# tsal_v1.net
KiCad netlist of a schematic drawn in Altium Designer
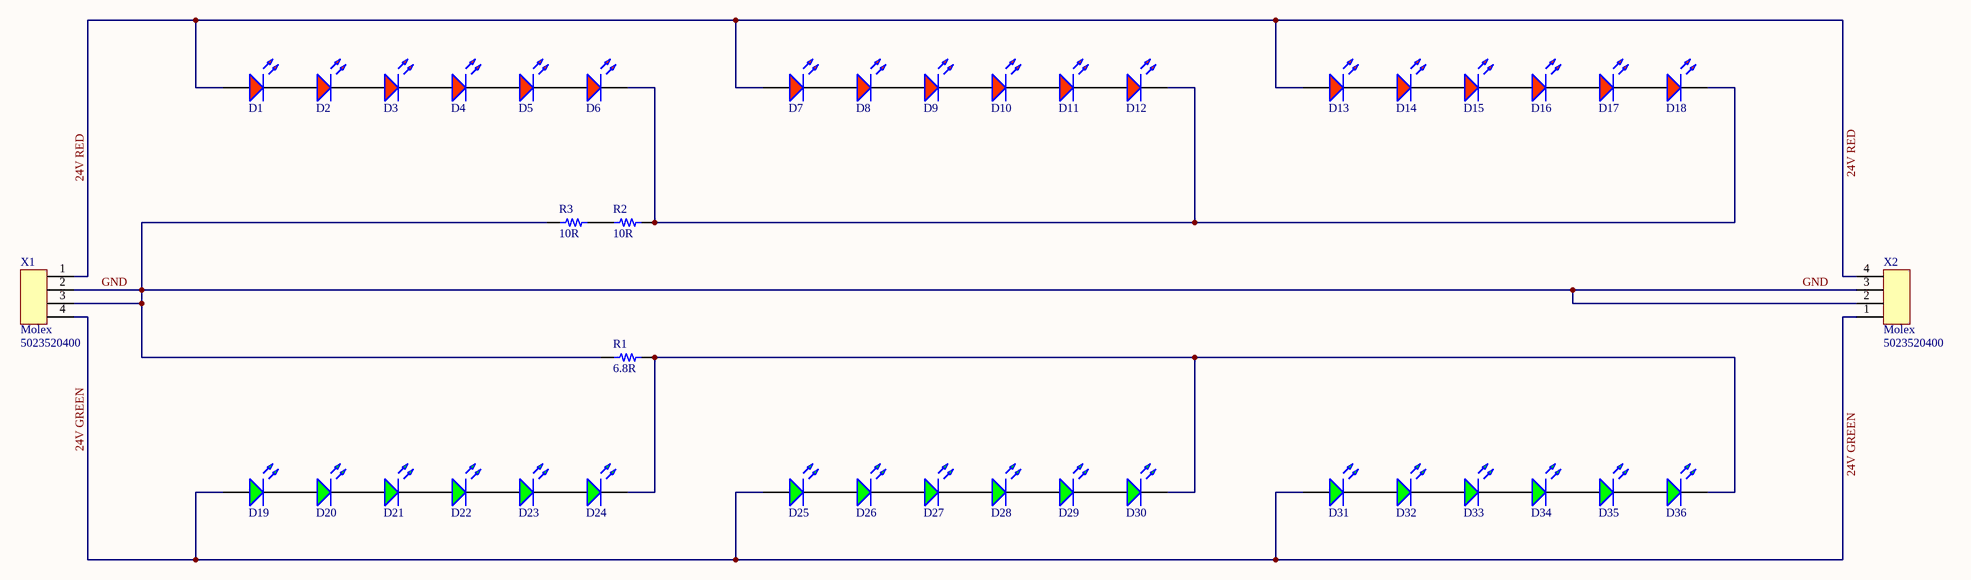
[diagram p0: tsal_v1.SchDoc]

(export (version "E")
  (design (tool "Eeschema 10.0.6"))
  (components
    (comp (ref "D1")
      (value "LED XLAMP RED 1616 SMD")
      (footprint "led red 0606")
      (description "LED Lighting Color Xlamp® XQ-A Red 625nm (620nm ~ 630nm) 0606 (1616 Metric)")
      (fields
        (field (name "MANUFACTURER") "Comchip Technology")
        (field (name "PART_NUMBER") "XQARED-02-0000-000000W01")
      )
      (libsource (lib "Diodes") (part "XQARED-02-0000-000000W01"))
    )
    (comp (ref "D2")
      (value "LED XLAMP RED 1616 SMD")
      (footprint "led red 0606")
      (description "LED Lighting Color Xlamp® XQ-A Red 625nm (620nm ~ 630nm) 0606 (1616 Metric)")
      (fields
        (field (name "MANUFACTURER") "Comchip Technology")
        (field (name "PART_NUMBER") "XQARED-02-0000-000000W01")
      )
      (libsource (lib "Diodes") (part "XQARED-02-0000-000000W01"))
    )
    (comp (ref "D3")
      (value "LED XLAMP RED 1616 SMD")
      (footprint "led red 0606")
      (description "LED Lighting Color Xlamp® XQ-A Red 625nm (620nm ~ 630nm) 0606 (1616 Metric)")
      (fields
        (field (name "MANUFACTURER") "Comchip Technology")
        (field (name "PART_NUMBER") "XQARED-02-0000-000000W01")
      )
      (libsource (lib "Diodes") (part "XQARED-02-0000-000000W01"))
    )
    (comp (ref "D4")
      (value "LED XLAMP RED 1616 SMD")
      (footprint "led red 0606")
      (description "LED Lighting Color Xlamp® XQ-A Red 625nm (620nm ~ 630nm) 0606 (1616 Metric)")
      (fields
        (field (name "MANUFACTURER") "Comchip Technology")
        (field (name "PART_NUMBER") "XQARED-02-0000-000000W01")
      )
      (libsource (lib "Diodes") (part "XQARED-02-0000-000000W01"))
    )
    (comp (ref "D5")
      (value "LED XLAMP RED 1616 SMD")
      (footprint "led red 0606")
      (description "LED Lighting Color Xlamp® XQ-A Red 625nm (620nm ~ 630nm) 0606 (1616 Metric)")
      (fields
        (field (name "MANUFACTURER") "Comchip Technology")
        (field (name "PART_NUMBER") "XQARED-02-0000-000000W01")
      )
      (libsource (lib "Diodes") (part "XQARED-02-0000-000000W01"))
    )
    (comp (ref "D6")
      (value "LED XLAMP RED 1616 SMD")
      (footprint "led red 0606")
      (description "LED Lighting Color Xlamp® XQ-A Red 625nm (620nm ~ 630nm) 0606 (1616 Metric)")
      (fields
        (field (name "MANUFACTURER") "Comchip Technology")
        (field (name "PART_NUMBER") "XQARED-02-0000-000000W01")
      )
      (libsource (lib "Diodes") (part "XQARED-02-0000-000000W01"))
    )
    (comp (ref "D7")
      (value "LED XLAMP RED 1616 SMD")
      (footprint "led red 0606")
      (description "LED Lighting Color Xlamp® XQ-A Red 625nm (620nm ~ 630nm) 0606 (1616 Metric)")
      (fields
        (field (name "MANUFACTURER") "Comchip Technology")
        (field (name "PART_NUMBER") "XQARED-02-0000-000000W01")
      )
      (libsource (lib "Diodes") (part "XQARED-02-0000-000000W01"))
    )
    (comp (ref "D8")
      (value "LED XLAMP RED 1616 SMD")
      (footprint "led red 0606")
      (description "LED Lighting Color Xlamp® XQ-A Red 625nm (620nm ~ 630nm) 0606 (1616 Metric)")
      (fields
        (field (name "MANUFACTURER") "Comchip Technology")
        (field (name "PART_NUMBER") "XQARED-02-0000-000000W01")
      )
      (libsource (lib "Diodes") (part "XQARED-02-0000-000000W01"))
    )
    (comp (ref "D9")
      (value "LED XLAMP RED 1616 SMD")
      (footprint "led red 0606")
      (description "LED Lighting Color Xlamp® XQ-A Red 625nm (620nm ~ 630nm) 0606 (1616 Metric)")
      (fields
        (field (name "MANUFACTURER") "Comchip Technology")
        (field (name "PART_NUMBER") "XQARED-02-0000-000000W01")
      )
      (libsource (lib "Diodes") (part "XQARED-02-0000-000000W01"))
    )
    (comp (ref "D10")
      (value "LED XLAMP RED 1616 SMD")
      (footprint "led red 0606")
      (description "LED Lighting Color Xlamp® XQ-A Red 625nm (620nm ~ 630nm) 0606 (1616 Metric)")
      (fields
        (field (name "MANUFACTURER") "Comchip Technology")
        (field (name "PART_NUMBER") "XQARED-02-0000-000000W01")
      )
      (libsource (lib "Diodes") (part "XQARED-02-0000-000000W01"))
    )
    (comp (ref "D11")
      (value "LED XLAMP RED 1616 SMD")
      (footprint "led red 0606")
      (description "LED Lighting Color Xlamp® XQ-A Red 625nm (620nm ~ 630nm) 0606 (1616 Metric)")
      (fields
        (field (name "MANUFACTURER") "Comchip Technology")
        (field (name "PART_NUMBER") "XQARED-02-0000-000000W01")
      )
      (libsource (lib "Diodes") (part "XQARED-02-0000-000000W01"))
    )
    (comp (ref "D12")
      (value "LED XLAMP RED 1616 SMD")
      (footprint "led red 0606")
      (description "LED Lighting Color Xlamp® XQ-A Red 625nm (620nm ~ 630nm) 0606 (1616 Metric)")
      (fields
        (field (name "MANUFACTURER") "Comchip Technology")
        (field (name "PART_NUMBER") "XQARED-02-0000-000000W01")
      )
      (libsource (lib "Diodes") (part "XQARED-02-0000-000000W01"))
    )
    (comp (ref "D13")
      (value "LED XLAMP RED 1616 SMD")
      (footprint "led red 0606")
      (description "LED Lighting Color Xlamp® XQ-A Red 625nm (620nm ~ 630nm) 0606 (1616 Metric)")
      (fields
        (field (name "MANUFACTURER") "Comchip Technology")
        (field (name "PART_NUMBER") "XQARED-02-0000-000000W01")
      )
      (libsource (lib "Diodes") (part "XQARED-02-0000-000000W01"))
    )
    (comp (ref "D14")
      (value "LED XLAMP RED 1616 SMD")
      (footprint "led red 0606")
      (description "LED Lighting Color Xlamp® XQ-A Red 625nm (620nm ~ 630nm) 0606 (1616 Metric)")
      (fields
        (field (name "MANUFACTURER") "Comchip Technology")
        (field (name "PART_NUMBER") "XQARED-02-0000-000000W01")
      )
      (libsource (lib "Diodes") (part "XQARED-02-0000-000000W01"))
    )
    (comp (ref "D15")
      (value "LED XLAMP RED 1616 SMD")
      (footprint "led red 0606")
      (description "LED Lighting Color Xlamp® XQ-A Red 625nm (620nm ~ 630nm) 0606 (1616 Metric)")
      (fields
        (field (name "MANUFACTURER") "Comchip Technology")
        (field (name "PART_NUMBER") "XQARED-02-0000-000000W01")
      )
      (libsource (lib "Diodes") (part "XQARED-02-0000-000000W01"))
    )
    (comp (ref "D16")
      (value "LED XLAMP RED 1616 SMD")
      (footprint "led red 0606")
      (description "LED Lighting Color Xlamp® XQ-A Red 625nm (620nm ~ 630nm) 0606 (1616 Metric)")
      (fields
        (field (name "MANUFACTURER") "Comchip Technology")
        (field (name "PART_NUMBER") "XQARED-02-0000-000000W01")
      )
      (libsource (lib "Diodes") (part "XQARED-02-0000-000000W01"))
    )
    (comp (ref "D17")
      (value "LED XLAMP RED 1616 SMD")
      (footprint "led red 0606")
      (description "LED Lighting Color Xlamp® XQ-A Red 625nm (620nm ~ 630nm) 0606 (1616 Metric)")
      (fields
        (field (name "MANUFACTURER") "Comchip Technology")
        (field (name "PART_NUMBER") "XQARED-02-0000-000000W01")
      )
      (libsource (lib "Diodes") (part "XQARED-02-0000-000000W01"))
    )
    (comp (ref "D18")
      (value "LED XLAMP RED 1616 SMD")
      (footprint "led red 0606")
      (description "LED Lighting Color Xlamp® XQ-A Red 625nm (620nm ~ 630nm) 0606 (1616 Metric)")
      (fields
        (field (name "MANUFACTURER") "Comchip Technology")
        (field (name "PART_NUMBER") "XQARED-02-0000-000000W01")
      )
      (libsource (lib "Diodes") (part "XQARED-02-0000-000000W01"))
    )
    (comp (ref "D19")
      (value "LED XLAMP GREEN 1616 SMD")
      (footprint "led red 0606")
      (description "LED Lighting Color Xlamp® XQ-A Green 528nm (520nm ~ 535nm) 0606 (1616 Metric)")
      (fields
        (field (name "MANUFACTURER") "Comchip Technology")
        (field (name "PART_NUMBER") "XQAGRN-02-0000-000000Z01")
      )
      (libsource (lib "Diodes") (part "XQAGRN-02-0000-000000Z01"))
    )
    (comp (ref "D20")
      (value "LED XLAMP GREEN 1616 SMD")
      (footprint "led red 0606")
      (description "LED Lighting Color Xlamp® XQ-A Green 528nm (520nm ~ 535nm) 0606 (1616 Metric)")
      (fields
        (field (name "MANUFACTURER") "Comchip Technology")
        (field (name "PART_NUMBER") "XQAGRN-02-0000-000000Z01")
      )
      (libsource (lib "Diodes") (part "XQAGRN-02-0000-000000Z01"))
    )
    (comp (ref "D21")
      (value "LED XLAMP GREEN 1616 SMD")
      (footprint "led red 0606")
      (description "LED Lighting Color Xlamp® XQ-A Green 528nm (520nm ~ 535nm) 0606 (1616 Metric)")
      (fields
        (field (name "MANUFACTURER") "Comchip Technology")
        (field (name "PART_NUMBER") "XQAGRN-02-0000-000000Z01")
      )
      (libsource (lib "Diodes") (part "XQAGRN-02-0000-000000Z01"))
    )
    (comp (ref "D22")
      (value "LED XLAMP GREEN 1616 SMD")
      (footprint "led red 0606")
      (description "LED Lighting Color Xlamp® XQ-A Green 528nm (520nm ~ 535nm) 0606 (1616 Metric)")
      (fields
        (field (name "MANUFACTURER") "Comchip Technology")
        (field (name "PART_NUMBER") "XQAGRN-02-0000-000000Z01")
      )
      (libsource (lib "Diodes") (part "XQAGRN-02-0000-000000Z01"))
    )
    (comp (ref "D23")
      (value "LED XLAMP GREEN 1616 SMD")
      (footprint "led red 0606")
      (description "LED Lighting Color Xlamp® XQ-A Green 528nm (520nm ~ 535nm) 0606 (1616 Metric)")
      (fields
        (field (name "MANUFACTURER") "Comchip Technology")
        (field (name "PART_NUMBER") "XQAGRN-02-0000-000000Z01")
      )
      (libsource (lib "Diodes") (part "XQAGRN-02-0000-000000Z01"))
    )
    (comp (ref "D24")
      (value "LED XLAMP GREEN 1616 SMD")
      (footprint "led red 0606")
      (description "LED Lighting Color Xlamp® XQ-A Green 528nm (520nm ~ 535nm) 0606 (1616 Metric)")
      (fields
        (field (name "MANUFACTURER") "Comchip Technology")
        (field (name "PART_NUMBER") "XQAGRN-02-0000-000000Z01")
      )
      (libsource (lib "Diodes") (part "XQAGRN-02-0000-000000Z01"))
    )
    (comp (ref "D25")
      (value "LED XLAMP GREEN 1616 SMD")
      (footprint "led red 0606")
      (description "LED Lighting Color Xlamp® XQ-A Green 528nm (520nm ~ 535nm) 0606 (1616 Metric)")
      (fields
        (field (name "MANUFACTURER") "Comchip Technology")
        (field (name "PART_NUMBER") "XQAGRN-02-0000-000000Z01")
      )
      (libsource (lib "Diodes") (part "XQAGRN-02-0000-000000Z01"))
    )
    (comp (ref "D26")
      (value "LED XLAMP GREEN 1616 SMD")
      (footprint "led red 0606")
      (description "LED Lighting Color Xlamp® XQ-A Green 528nm (520nm ~ 535nm) 0606 (1616 Metric)")
      (fields
        (field (name "MANUFACTURER") "Comchip Technology")
        (field (name "PART_NUMBER") "XQAGRN-02-0000-000000Z01")
      )
      (libsource (lib "Diodes") (part "XQAGRN-02-0000-000000Z01"))
    )
    (comp (ref "D27")
      (value "LED XLAMP GREEN 1616 SMD")
      (footprint "led red 0606")
      (description "LED Lighting Color Xlamp® XQ-A Green 528nm (520nm ~ 535nm) 0606 (1616 Metric)")
      (fields
        (field (name "MANUFACTURER") "Comchip Technology")
        (field (name "PART_NUMBER") "XQAGRN-02-0000-000000Z01")
      )
      (libsource (lib "Diodes") (part "XQAGRN-02-0000-000000Z01"))
    )
    (comp (ref "D28")
      (value "LED XLAMP GREEN 1616 SMD")
      (footprint "led red 0606")
      (description "LED Lighting Color Xlamp® XQ-A Green 528nm (520nm ~ 535nm) 0606 (1616 Metric)")
      (fields
        (field (name "MANUFACTURER") "Comchip Technology")
        (field (name "PART_NUMBER") "XQAGRN-02-0000-000000Z01")
      )
      (libsource (lib "Diodes") (part "XQAGRN-02-0000-000000Z01"))
    )
    (comp (ref "D29")
      (value "LED XLAMP GREEN 1616 SMD")
      (footprint "led red 0606")
      (description "LED Lighting Color Xlamp® XQ-A Green 528nm (520nm ~ 535nm) 0606 (1616 Metric)")
      (fields
        (field (name "MANUFACTURER") "Comchip Technology")
        (field (name "PART_NUMBER") "XQAGRN-02-0000-000000Z01")
      )
      (libsource (lib "Diodes") (part "XQAGRN-02-0000-000000Z01"))
    )
    (comp (ref "D30")
      (value "LED XLAMP GREEN 1616 SMD")
      (footprint "led red 0606")
      (description "LED Lighting Color Xlamp® XQ-A Green 528nm (520nm ~ 535nm) 0606 (1616 Metric)")
      (fields
        (field (name "MANUFACTURER") "Comchip Technology")
        (field (name "PART_NUMBER") "XQAGRN-02-0000-000000Z01")
      )
      (libsource (lib "Diodes") (part "XQAGRN-02-0000-000000Z01"))
    )
    (comp (ref "D31")
      (value "LED XLAMP GREEN 1616 SMD")
      (footprint "led red 0606")
      (description "LED Lighting Color Xlamp® XQ-A Green 528nm (520nm ~ 535nm) 0606 (1616 Metric)")
      (fields
        (field (name "MANUFACTURER") "Comchip Technology")
        (field (name "PART_NUMBER") "XQAGRN-02-0000-000000Z01")
      )
      (libsource (lib "Diodes") (part "XQAGRN-02-0000-000000Z01"))
    )
    (comp (ref "D32")
      (value "LED XLAMP GREEN 1616 SMD")
      (footprint "led red 0606")
      (description "LED Lighting Color Xlamp® XQ-A Green 528nm (520nm ~ 535nm) 0606 (1616 Metric)")
      (fields
        (field (name "MANUFACTURER") "Comchip Technology")
        (field (name "PART_NUMBER") "XQAGRN-02-0000-000000Z01")
      )
      (libsource (lib "Diodes") (part "XQAGRN-02-0000-000000Z01"))
    )
    (comp (ref "D33")
      (value "LED XLAMP GREEN 1616 SMD")
      (footprint "led red 0606")
      (description "LED Lighting Color Xlamp® XQ-A Green 528nm (520nm ~ 535nm) 0606 (1616 Metric)")
      (fields
        (field (name "MANUFACTURER") "Comchip Technology")
        (field (name "PART_NUMBER") "XQAGRN-02-0000-000000Z01")
      )
      (libsource (lib "Diodes") (part "XQAGRN-02-0000-000000Z01"))
    )
    (comp (ref "D34")
      (value "LED XLAMP GREEN 1616 SMD")
      (footprint "led red 0606")
      (description "LED Lighting Color Xlamp® XQ-A Green 528nm (520nm ~ 535nm) 0606 (1616 Metric)")
      (fields
        (field (name "MANUFACTURER") "Comchip Technology")
        (field (name "PART_NUMBER") "XQAGRN-02-0000-000000Z01")
      )
      (libsource (lib "Diodes") (part "XQAGRN-02-0000-000000Z01"))
    )
    (comp (ref "D35")
      (value "LED XLAMP GREEN 1616 SMD")
      (footprint "led red 0606")
      (description "LED Lighting Color Xlamp® XQ-A Green 528nm (520nm ~ 535nm) 0606 (1616 Metric)")
      (fields
        (field (name "MANUFACTURER") "Comchip Technology")
        (field (name "PART_NUMBER") "XQAGRN-02-0000-000000Z01")
      )
      (libsource (lib "Diodes") (part "XQAGRN-02-0000-000000Z01"))
    )
    (comp (ref "D36")
      (value "LED XLAMP GREEN 1616 SMD")
      (footprint "led red 0606")
      (description "LED Lighting Color Xlamp® XQ-A Green 528nm (520nm ~ 535nm) 0606 (1616 Metric)")
      (fields
        (field (name "MANUFACTURER") "Comchip Technology")
        (field (name "PART_NUMBER") "XQAGRN-02-0000-000000Z01")
      )
      (libsource (lib "Diodes") (part "XQAGRN-02-0000-000000Z01"))
    )
    (comp (ref "R1")
      (value "6.8R")
      (footprint "R2512 pad under")
      (description "6.8 Ohms ±1% 16W Chip Resistor 2512 (6432 Metric) Moisture Resistant Thin Film")
      (fields (field (name "MANUFACTURER") "Susumu") (field (name "POWER") "16W"))
      (libsource (lib "Resistors") (part "RES 2512 6.8R 1% 16W"))
    )
    (comp (ref "R2")
      (value "10R")
      (footprint "R2512 pad under")
      (description "10 Ohms ±1% 16W Chip Resistor 2512 (6432 Metric) Moisture Resistant Thin Film")
      (fields (field (name "MANUFACTURER") "Susumu") (field (name "POWER") "16W"))
      (libsource (lib "Resistors") (part "RES 2512 10R 1% 16W"))
    )
    (comp (ref "R3")
      (value "10R")
      (footprint "R2512 pad under")
      (description "10 Ohms ±1% 16W Chip Resistor 2512 (6432 Metric) Moisture Resistant Thin Film")
      (fields (field (name "MANUFACTURER") "Susumu") (field (name "POWER") "16W"))
      (libsource (lib "Resistors") (part "RES 2512 10R 1% 16W"))
    )
    (comp (ref "X1")
      (value "Connector")
      (footprint "5023520400")
      (description "Molex DuraClik, 4 pos, RA")
      (fields (field (name "MANUFACTURER") "Molex") (field (name "PART_NUMBER") "5023520400"))
      (libsource (lib "") (part "5023520400_1"))
    )
    (comp (ref "X2")
      (value "Connector")
      (footprint "5023520400")
      (description "Molex DuraClik, 4 pos, RA")
      (fields (field (name "MANUFACTURER") "Molex") (field (name "PART_NUMBER") "5023520400"))
      (libsource (lib "Connectors") (part "5023520400"))
    )
  )
  (nets
    (net (code "1") (name "/24V GREEN") (class "Default")
      (node (ref "D19") (pin "1") (pinfunction "A_1") (pintype "passive"))
      (node (ref "D25") (pin "1") (pinfunction "A_1") (pintype "passive"))
      (node (ref "D31") (pin "1") (pinfunction "A_1") (pintype "passive"))
      (node (ref "X1") (pin "4") (pinfunction "4_4") (pintype "passive"))
      (node (ref "X2") (pin "1") (pinfunction "1_1") (pintype "passive"))
    )
    (net (code "2") (name "/24V RED") (class "Default")
      (node (ref "D1") (pin "1") (pinfunction "1_1") (pintype "passive"))
      (node (ref "D13") (pin "1") (pinfunction "1_1") (pintype "passive"))
      (node (ref "D7") (pin "1") (pinfunction "1_1") (pintype "passive"))
      (node (ref "X1") (pin "1") (pinfunction "1_1") (pintype "passive"))
      (node (ref "X2") (pin "4") (pinfunction "4_4") (pintype "passive"))
    )
    (net (code "3") (name "/GND") (class "Default")
      (node (ref "R1") (pin "1") (pinfunction "1_1") (pintype "passive"))
      (node (ref "R3") (pin "1") (pinfunction "1_1") (pintype "passive"))
      (node (ref "X1") (pin "2") (pinfunction "2_2") (pintype "passive"))
      (node (ref "X1") (pin "3") (pinfunction "3_3") (pintype "passive"))
      (node (ref "X2") (pin "2") (pinfunction "2_2") (pintype "passive"))
      (node (ref "X2") (pin "3") (pinfunction "3_3") (pintype "passive"))
    )
    (net (code "4") (name "Net-(D1-Pad2)") (class "Default")
      (node (ref "D1") (pin "2") (pinfunction "2_2") (pintype "passive"))
      (node (ref "D2") (pin "1") (pinfunction "1_1") (pintype "passive"))
    )
    (net (code "5") (name "Net-(D2-Pad2)") (class "Default")
      (node (ref "D2") (pin "2") (pinfunction "2_2") (pintype "passive"))
      (node (ref "D3") (pin "1") (pinfunction "1_1") (pintype "passive"))
    )
    (net (code "6") (name "Net-(D3-Pad2)") (class "Default")
      (node (ref "D3") (pin "2") (pinfunction "2_2") (pintype "passive"))
      (node (ref "D4") (pin "1") (pinfunction "1_1") (pintype "passive"))
    )
    (net (code "7") (name "Net-(D4-Pad2)") (class "Default")
      (node (ref "D4") (pin "2") (pinfunction "2_2") (pintype "passive"))
      (node (ref "D5") (pin "1") (pinfunction "1_1") (pintype "passive"))
    )
    (net (code "8") (name "Net-(D5-Pad2)") (class "Default")
      (node (ref "D5") (pin "2") (pinfunction "2_2") (pintype "passive"))
      (node (ref "D6") (pin "1") (pinfunction "1_1") (pintype "passive"))
    )
    (net (code "9") (name "Net-(D7-Pad2)") (class "Default")
      (node (ref "D7") (pin "2") (pinfunction "2_2") (pintype "passive"))
      (node (ref "D8") (pin "1") (pinfunction "1_1") (pintype "passive"))
    )
    (net (code "10") (name "Net-(D8-Pad2)") (class "Default")
      (node (ref "D8") (pin "2") (pinfunction "2_2") (pintype "passive"))
      (node (ref "D9") (pin "1") (pinfunction "1_1") (pintype "passive"))
    )
    (net (code "11") (name "Net-(D10-Pad1)") (class "Default")
      (node (ref "D10") (pin "1") (pinfunction "1_1") (pintype "passive"))
      (node (ref "D9") (pin "2") (pinfunction "2_2") (pintype "passive"))
    )
    (net (code "12") (name "Net-(D10-Pad2)") (class "Default")
      (node (ref "D10") (pin "2") (pinfunction "2_2") (pintype "passive"))
      (node (ref "D11") (pin "1") (pinfunction "1_1") (pintype "passive"))
    )
    (net (code "13") (name "Net-(D11-Pad2)") (class "Default")
      (node (ref "D11") (pin "2") (pinfunction "2_2") (pintype "passive"))
      (node (ref "D12") (pin "1") (pinfunction "1_1") (pintype "passive"))
    )
    (net (code "14") (name "Net-(D12-Pad2)") (class "Default")
      (node (ref "D12") (pin "2") (pinfunction "2_2") (pintype "passive"))
      (node (ref "D18") (pin "2") (pinfunction "2_2") (pintype "passive"))
      (node (ref "D6") (pin "2") (pinfunction "2_2") (pintype "passive"))
      (node (ref "R2") (pin "2") (pinfunction "2_2") (pintype "passive"))
    )
    (net (code "15") (name "Net-(D13-Pad2)") (class "Default")
      (node (ref "D13") (pin "2") (pinfunction "2_2") (pintype "passive"))
      (node (ref "D14") (pin "1") (pinfunction "1_1") (pintype "passive"))
    )
    (net (code "16") (name "Net-(D14-Pad2)") (class "Default")
      (node (ref "D14") (pin "2") (pinfunction "2_2") (pintype "passive"))
      (node (ref "D15") (pin "1") (pinfunction "1_1") (pintype "passive"))
    )
    (net (code "17") (name "Net-(D15-Pad2)") (class "Default")
      (node (ref "D15") (pin "2") (pinfunction "2_2") (pintype "passive"))
      (node (ref "D16") (pin "1") (pinfunction "1_1") (pintype "passive"))
    )
    (net (code "18") (name "Net-(D16-Pad2)") (class "Default")
      (node (ref "D16") (pin "2") (pinfunction "2_2") (pintype "passive"))
      (node (ref "D17") (pin "1") (pinfunction "1_1") (pintype "passive"))
    )
    (net (code "19") (name "Net-(D17-Pad2)") (class "Default")
      (node (ref "D17") (pin "2") (pinfunction "2_2") (pintype "passive"))
      (node (ref "D18") (pin "1") (pinfunction "1_1") (pintype "passive"))
    )
    (net (code "20") (name "Net-(D19-K)") (class "Default")
      (node (ref "D19") (pin "2") (pinfunction "K_2") (pintype "passive"))
      (node (ref "D20") (pin "1") (pinfunction "A_1") (pintype "passive"))
    )
    (net (code "21") (name "Net-(D20-K)") (class "Default")
      (node (ref "D20") (pin "2") (pinfunction "K_2") (pintype "passive"))
      (node (ref "D21") (pin "1") (pinfunction "A_1") (pintype "passive"))
    )
    (net (code "22") (name "Net-(D21-K)") (class "Default")
      (node (ref "D21") (pin "2") (pinfunction "K_2") (pintype "passive"))
      (node (ref "D22") (pin "1") (pinfunction "A_1") (pintype "passive"))
    )
    (net (code "23") (name "Net-(D22-K)") (class "Default")
      (node (ref "D22") (pin "2") (pinfunction "K_2") (pintype "passive"))
      (node (ref "D23") (pin "1") (pinfunction "A_1") (pintype "passive"))
    )
    (net (code "24") (name "Net-(D23-K)") (class "Default")
      (node (ref "D23") (pin "2") (pinfunction "K_2") (pintype "passive"))
      (node (ref "D24") (pin "1") (pinfunction "A_1") (pintype "passive"))
    )
    (net (code "25") (name "Net-(D24-K)") (class "Default")
      (node (ref "D24") (pin "2") (pinfunction "K_2") (pintype "passive"))
      (node (ref "D30") (pin "2") (pinfunction "K_2") (pintype "passive"))
      (node (ref "D36") (pin "2") (pinfunction "K_2") (pintype "passive"))
      (node (ref "R1") (pin "2") (pinfunction "2_2") (pintype "passive"))
    )
    (net (code "26") (name "Net-(D25-K)") (class "Default")
      (node (ref "D25") (pin "2") (pinfunction "K_2") (pintype "passive"))
      (node (ref "D26") (pin "1") (pinfunction "A_1") (pintype "passive"))
    )
    (net (code "27") (name "Net-(D26-K)") (class "Default")
      (node (ref "D26") (pin "2") (pinfunction "K_2") (pintype "passive"))
      (node (ref "D27") (pin "1") (pinfunction "A_1") (pintype "passive"))
    )
    (net (code "28") (name "Net-(D27-K)") (class "Default")
      (node (ref "D27") (pin "2") (pinfunction "K_2") (pintype "passive"))
      (node (ref "D28") (pin "1") (pinfunction "A_1") (pintype "passive"))
    )
    (net (code "29") (name "Net-(D28-K)") (class "Default")
      (node (ref "D28") (pin "2") (pinfunction "K_2") (pintype "passive"))
      (node (ref "D29") (pin "1") (pinfunction "A_1") (pintype "passive"))
    )
    (net (code "30") (name "Net-(D29-K)") (class "Default")
      (node (ref "D29") (pin "2") (pinfunction "K_2") (pintype "passive"))
      (node (ref "D30") (pin "1") (pinfunction "A_1") (pintype "passive"))
    )
    (net (code "31") (name "Net-(D31-K)") (class "Default")
      (node (ref "D31") (pin "2") (pinfunction "K_2") (pintype "passive"))
      (node (ref "D32") (pin "1") (pinfunction "A_1") (pintype "passive"))
    )
    (net (code "32") (name "Net-(D32-K)") (class "Default")
      (node (ref "D32") (pin "2") (pinfunction "K_2") (pintype "passive"))
      (node (ref "D33") (pin "1") (pinfunction "A_1") (pintype "passive"))
    )
    (net (code "33") (name "Net-(D33-K)") (class "Default")
      (node (ref "D33") (pin "2") (pinfunction "K_2") (pintype "passive"))
      (node (ref "D34") (pin "1") (pinfunction "A_1") (pintype "passive"))
    )
    (net (code "34") (name "Net-(D34-K)") (class "Default")
      (node (ref "D34") (pin "2") (pinfunction "K_2") (pintype "passive"))
      (node (ref "D35") (pin "1") (pinfunction "A_1") (pintype "passive"))
    )
    (net (code "35") (name "Net-(D35-K)") (class "Default")
      (node (ref "D35") (pin "2") (pinfunction "K_2") (pintype "passive"))
      (node (ref "D36") (pin "1") (pinfunction "A_1") (pintype "passive"))
    )
    (net (code "36") (name "Net-(R2-Pad1)") (class "Default")
      (node (ref "R2") (pin "1") (pinfunction "1_1") (pintype "passive"))
      (node (ref "R3") (pin "2") (pinfunction "2_2") (pintype "passive"))
    )
  )
)
